# LoadSwitch.net
KiCad netlist of a schematic drawn in Altium Designer
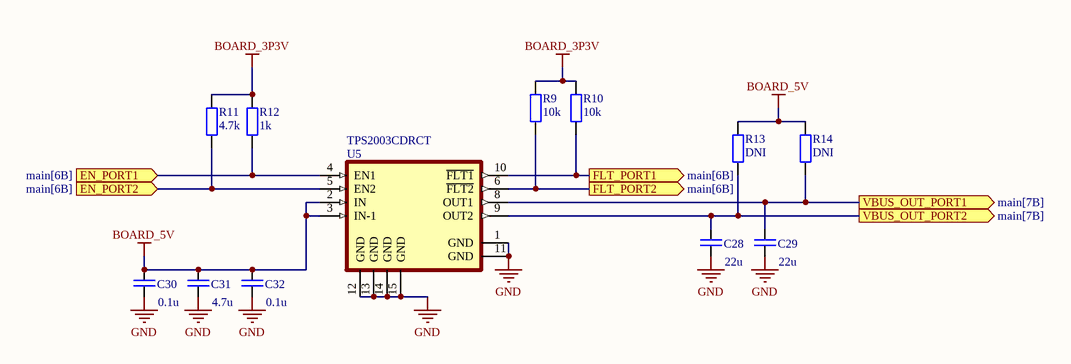
[diagram p0: LoadSwitch.SchDoc]

(export (version "E")
  (design (tool "Eeschema 10.0.6"))
  (components
    (comp (ref "C28")
      (value "22u")
      (footprint "CAP_0603_N")
      (fields (field (name "Comment") "comment"))
      (libsource (lib "USB-HUB1") (part "Capacitor non-polarized"))
    )
    (comp (ref "C29")
      (value "22u")
      (footprint "CAP_0603_N")
      (fields (field (name "Comment") "comment"))
      (libsource (lib "USB-HUB1") (part "Capacitor non-polarized"))
    )
    (comp (ref "C30")
      (value "0.1u")
      (footprint "CAP_0603_N")
      (fields (field (name "Comment") "comment"))
      (libsource (lib "USB-HUB1") (part "Capacitor non-polarized"))
    )
    (comp (ref "C31")
      (value "4.7u")
      (footprint "CAP_0603_N")
      (fields (field (name "Comment") "comment"))
      (libsource (lib "USB-HUB1") (part "Capacitor non-polarized"))
    )
    (comp (ref "C32")
      (value "0.1u")
      (footprint "CAP_0603_N")
      (fields (field (name "Comment") "comment"))
      (libsource (lib "USB-HUB1") (part "Capacitor non-polarized"))
    )
    (comp (ref "R9")
      (value "10k")
      (footprint "SMD_0603_N")
      (fields (field (name "Comment") "comment"))
      (libsource (lib "USB-HUB1") (part "Resistor"))
    )
    (comp (ref "R10")
      (value "10k")
      (footprint "SMD_0603_N")
      (fields (field (name "Comment") "comment"))
      (libsource (lib "USB-HUB1") (part "Resistor"))
    )
    (comp (ref "R11")
      (value "4.7k")
      (footprint "SMD_0603_N")
      (fields (field (name "Comment") "comment"))
      (libsource (lib "USB-HUB1") (part "Resistor"))
    )
    (comp (ref "R12")
      (value "1k")
      (footprint "SMD_0603_N")
      (fields (field (name "Comment") "comment"))
      (libsource (lib "USB-HUB1") (part "Resistor"))
    )
    (comp (ref "R13")
      (value "DNI")
      (footprint "SMD_0603_N")
      (fields (field (name "Comment") "comment"))
      (libsource (lib "USB-HUB1") (part "Resistor"))
    )
    (comp (ref "R14")
      (value "DNI")
      (footprint "SMD_0603_N")
      (fields (field (name "Comment") "comment"))
      (libsource (lib "USB-HUB1") (part "Resistor"))
    )
    (comp (ref "U5")
      (value "TPS2003CDRCT")
      (footprint "VREG_V62/16624-01YE")
      (libsource (lib "USB-HUB1") (part "TPS2003CDRCT"))
    )
  )
  (nets
    (net (code "1") (name "/EN_PORT1") (class "Default")
      (node (ref "R12") (pin "1") (pintype "passive"))
      (node (ref "U5") (pin "4") (pinfunction "EN1_4") (pintype "input"))
    )
    (net (code "2") (name "/EN_PORT2") (class "Default")
      (node (ref "R11") (pin "1") (pintype "passive"))
      (node (ref "U5") (pin "5") (pinfunction "EN2_5") (pintype "input"))
    )
    (net (code "3") (name "/FLT_PORT1") (class "Default")
      (node (ref "R10") (pin "1") (pintype "passive"))
      (node (ref "U5") (pin "10") (pinfunction "~{FLT1}_10") (pintype "output"))
    )
    (net (code "4") (name "/FLT_PORT2") (class "Default")
      (node (ref "R9") (pin "1") (pintype "passive"))
      (node (ref "U5") (pin "6") (pinfunction "~{FLT2}_6") (pintype "output"))
    )
    (net (code "5") (name "/VBUS_OUT_PORT1") (class "Default")
      (node (ref "C29") (pin "1") (pinfunction "1_1") (pintype "passive"))
      (node (ref "R14") (pin "1") (pintype "passive"))
      (node (ref "U5") (pin "8") (pinfunction "OUT1_8") (pintype "output"))
    )
    (net (code "6") (name "/VBUS_OUT_PORT2") (class "Default")
      (node (ref "C28") (pin "1") (pinfunction "1_1") (pintype "passive"))
      (node (ref "R13") (pin "1") (pintype "passive"))
      (node (ref "U5") (pin "9") (pinfunction "OUT2_9") (pintype "output"))
    )
    (net (code "7") (name "BOARD_3P3V") (class "Default")
      (node (ref "R10") (pin "2") (pintype "passive"))
      (node (ref "R11") (pin "2") (pintype "passive"))
      (node (ref "R12") (pin "2") (pintype "passive"))
      (node (ref "R9") (pin "2") (pintype "passive"))
    )
    (net (code "8") (name "BOARD_5V") (class "Default")
      (node (ref "C30") (pin "1") (pinfunction "1_1") (pintype "passive"))
      (node (ref "C31") (pin "1") (pinfunction "1_1") (pintype "passive"))
      (node (ref "C32") (pin "1") (pinfunction "1_1") (pintype "passive"))
      (node (ref "R13") (pin "2") (pintype "passive"))
      (node (ref "R14") (pin "2") (pintype "passive"))
      (node (ref "U5") (pin "2") (pinfunction "IN_2") (pintype "input"))
      (node (ref "U5") (pin "3") (pinfunction "IN-1_3") (pintype "input"))
    )
    (net (code "9") (name "GND") (class "Default")
      (node (ref "C28") (pin "2") (pinfunction "2_2") (pintype "passive"))
      (node (ref "C29") (pin "2") (pinfunction "2_2") (pintype "passive"))
      (node (ref "C30") (pin "2") (pinfunction "2_2") (pintype "passive"))
      (node (ref "C31") (pin "2") (pinfunction "2_2") (pintype "passive"))
      (node (ref "C32") (pin "2") (pinfunction "2_2") (pintype "passive"))
      (node (ref "U5") (pin "1") (pinfunction "GND_1") (pintype "power_in"))
      (node (ref "U5") (pin "11") (pinfunction "GND_11") (pintype "power_in"))
      (node (ref "U5") (pin "12") (pinfunction "GND_12") (pintype "power_in"))
      (node (ref "U5") (pin "13") (pinfunction "GND_13") (pintype "power_in"))
      (node (ref "U5") (pin "14") (pinfunction "GND_14") (pintype "power_in"))
      (node (ref "U5") (pin "15") (pinfunction "GND_15") (pintype "power_in"))
    )
  )
)
